# MJ818_original.net
KiCad netlist of a schematic drawn in EAGLE
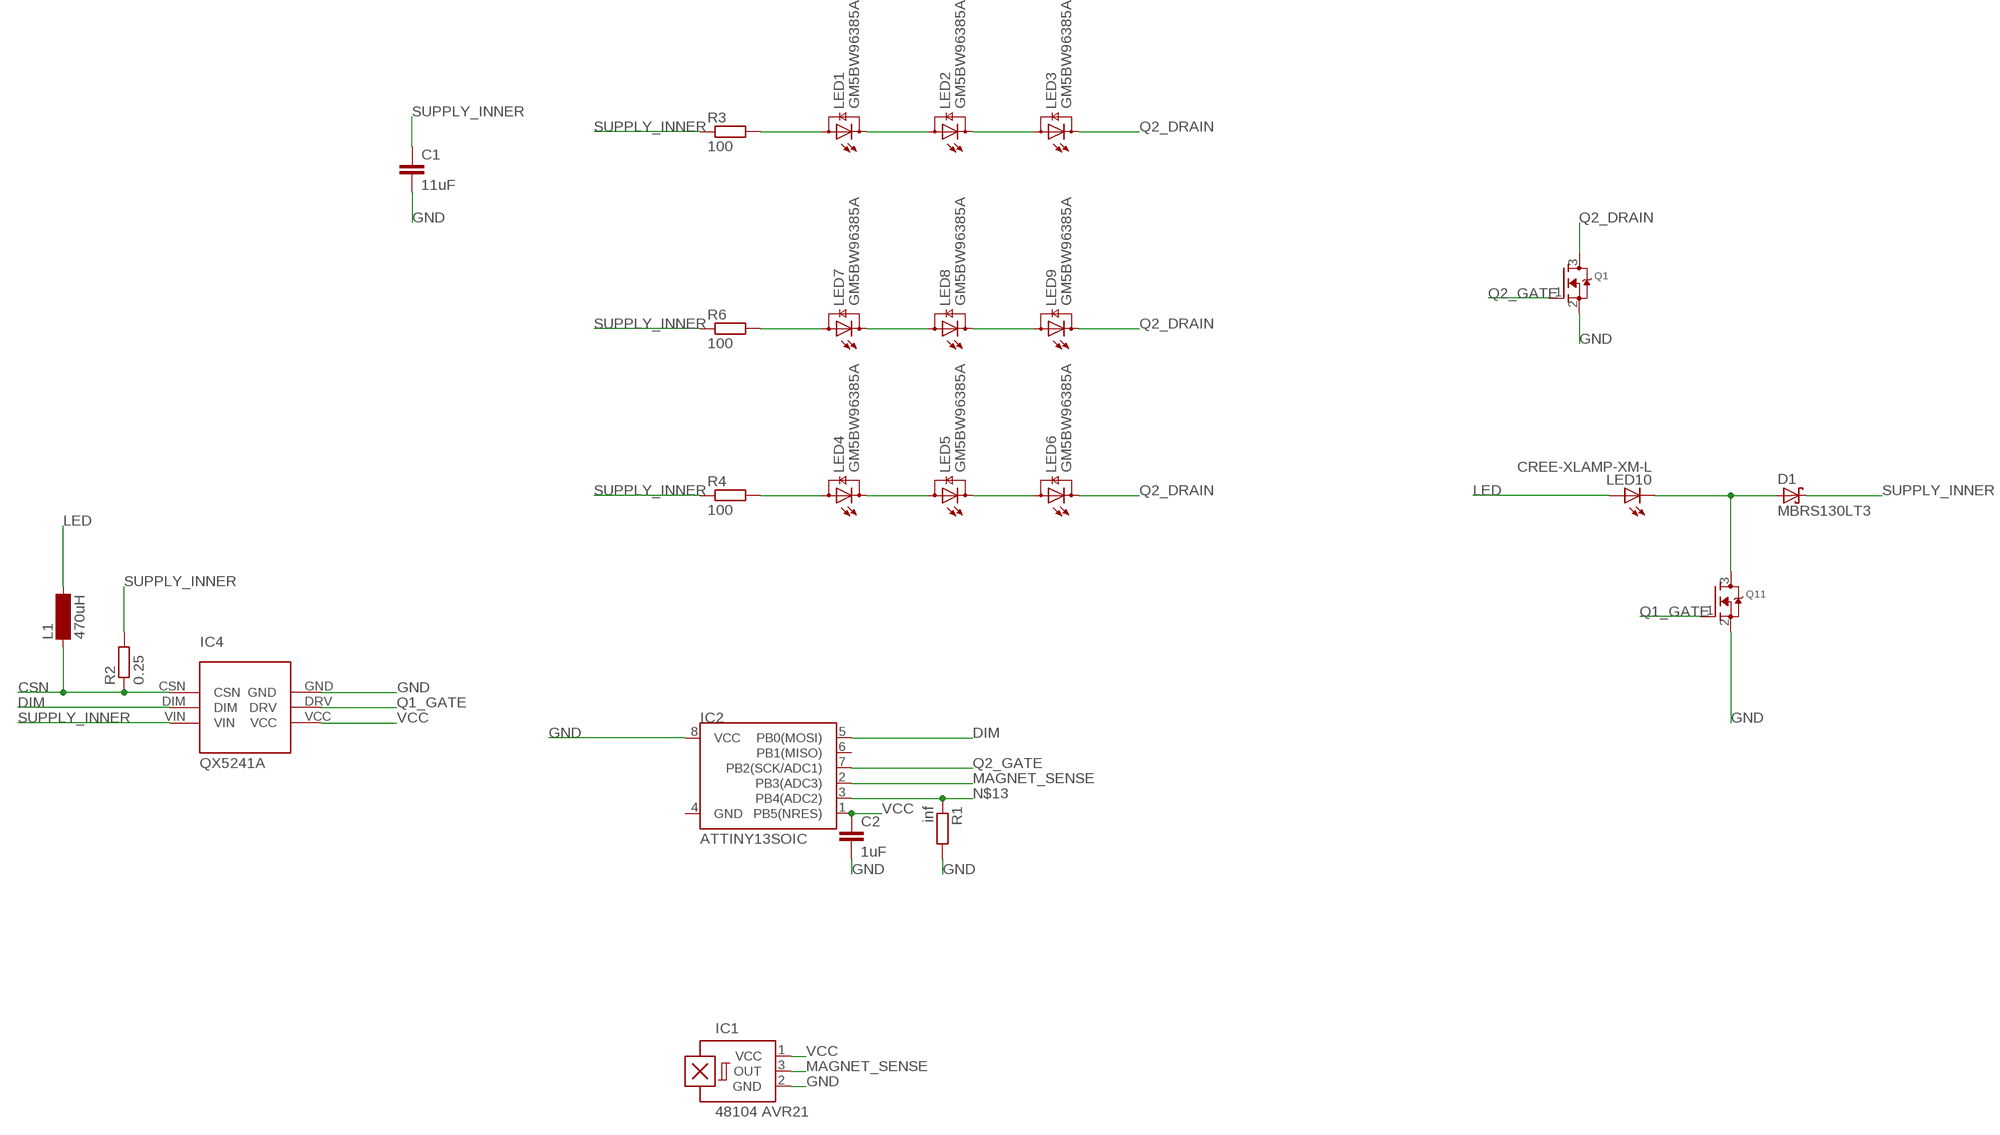
[diagram p0: schematic, sheet 1]

(export (version "E")
  (design (tool "Eeschema 10.0.6"))
  (components
    (comp (ref "C1")
      (value "11uF")
      (footprint "eagle-import:C3225")
      (libsource (lib "eagle-import") (part "C-EUC3225"))
    )
    (comp (ref "C2")
      (value "1uF")
      (footprint "eagle-import:C2012")
      (libsource (lib "eagle-import") (part "C-EUC2012"))
    )
    (comp (ref "D1")
      (value "MBRS130LT3")
      (footprint "eagle-import:SMB")
      (libsource (lib "eagle-import") (part "MBRS130LT3"))
    )
    (comp (ref "IC1")
      (value "48104 AVR21")
      (footprint "eagle-import:SIP3-UA")
      (libsource (lib "eagle-import") (part "A12?UA02"))
    )
    (comp (ref "IC2")
      (value "ATTINY13SOIC")
      (footprint "eagle-import:SO08_MCU")
      (libsource (lib "eagle-import") (part "ATTINY13SOIC"))
    )
    (comp (ref "IC4")
      (value "QX5241A")
      (footprint "eagle-import:SOT-23-6")
      (libsource (lib "eagle-import") (part "QX5241A"))
    )
    (comp (ref "L1")
      (value "470uH")
      (footprint "eagle-import:MS50")
      (libsource (lib "eagle-import") (part "MS50"))
    )
    (comp (ref "LED1")
      (value "GM5BW96385A")
      (footprint "eagle-import:GM5BW96385A")
      (libsource (lib "eagle-import") (part "GM5BW96385A"))
    )
    (comp (ref "LED2")
      (value "GM5BW96385A")
      (footprint "eagle-import:GM5BW96385A")
      (libsource (lib "eagle-import") (part "GM5BW96385A"))
    )
    (comp (ref "LED3")
      (value "GM5BW96385A")
      (footprint "eagle-import:GM5BW96385A")
      (libsource (lib "eagle-import") (part "GM5BW96385A"))
    )
    (comp (ref "LED4")
      (value "GM5BW96385A")
      (footprint "eagle-import:GM5BW96385A")
      (libsource (lib "eagle-import") (part "GM5BW96385A"))
    )
    (comp (ref "LED5")
      (value "GM5BW96385A")
      (footprint "eagle-import:GM5BW96385A")
      (libsource (lib "eagle-import") (part "GM5BW96385A"))
    )
    (comp (ref "LED6")
      (value "GM5BW96385A")
      (footprint "eagle-import:GM5BW96385A")
      (libsource (lib "eagle-import") (part "GM5BW96385A"))
    )
    (comp (ref "LED7")
      (value "GM5BW96385A")
      (footprint "eagle-import:GM5BW96385A")
      (libsource (lib "eagle-import") (part "GM5BW96385A"))
    )
    (comp (ref "LED8")
      (value "GM5BW96385A")
      (footprint "eagle-import:GM5BW96385A")
      (libsource (lib "eagle-import") (part "GM5BW96385A"))
    )
    (comp (ref "LED9")
      (value "GM5BW96385A")
      (footprint "eagle-import:GM5BW96385A")
      (libsource (lib "eagle-import") (part "GM5BW96385A"))
    )
    (comp (ref "LED10")
      (value "CREE-XLAMP-XM-L")
      (footprint "eagle-import:CREE-XLAMP-XM-L")
      (libsource (lib "eagle-import") (part "CREE-XLAMP-XM-L"))
    )
    (comp (ref "Q1")
      (value "MOSFET-NWAVE")
      (footprint "eagle-import:SOT23-W")
      (libsource (lib "eagle-import") (part "MOSFET-NWAVE"))
    )
    (comp (ref "Q11")
      (value "MOSFET-NWAVE")
      (footprint "eagle-import:SOT23-W")
      (libsource (lib "eagle-import") (part "MOSFET-NWAVE"))
    )
    (comp (ref "R1")
      (value "inf")
      (footprint "eagle-import:R3216")
      (libsource (lib "eagle-import") (part "R-EU_R3216"))
    )
    (comp (ref "R2")
      (value "0.25")
      (footprint "eagle-import:R3216")
      (libsource (lib "eagle-import") (part "R-EU_R3216"))
    )
    (comp (ref "R3")
      (value "100")
      (footprint "eagle-import:R3216")
      (libsource (lib "eagle-import") (part "R-EU_R3216"))
    )
    (comp (ref "R4")
      (value "100")
      (footprint "eagle-import:R3216")
      (libsource (lib "eagle-import") (part "R-EU_R3216"))
    )
    (comp (ref "R6")
      (value "100")
      (footprint "eagle-import:R3216")
      (libsource (lib "eagle-import") (part "R-EU_R3216"))
    )
  )
  (nets
    (net (code "1") (name "/CSN") (class "Default")
      (node (ref "IC4") (pin "CSN") (pinfunction "CSN_CSN") (pintype "bidirectional"))
      (node (ref "L1") (pin "1") (pinfunction "1_1") (pintype "passive"))
      (node (ref "R2") (pin "1") (pinfunction "1_1") (pintype "passive"))
    )
    (net (code "2") (name "/DIM") (class "Default")
      (node (ref "IC2") (pin "5") (pinfunction "PB0(MOSI)_5") (pintype "bidirectional"))
      (node (ref "IC4") (pin "DIM") (pinfunction "DIM_DIM") (pintype "bidirectional"))
    )
    (net (code "3") (name "/GND") (class "Default")
      (node (ref "C1") (pin "2") (pinfunction "2_2") (pintype "passive"))
      (node (ref "C2") (pin "2") (pinfunction "2_2") (pintype "passive"))
      (node (ref "IC1") (pin "2") (pinfunction "GND_2") (pintype "power_in"))
      (node (ref "IC2") (pin "8") (pinfunction "VCC_8") (pintype "bidirectional"))
      (node (ref "IC4") (pin "GND") (pinfunction "GND_GND") (pintype "bidirectional"))
      (node (ref "Q1") (pin "2") (pinfunction "S_2") (pintype "bidirectional"))
      (node (ref "Q11") (pin "2") (pinfunction "S_2") (pintype "bidirectional"))
      (node (ref "R1") (pin "2") (pinfunction "2_2") (pintype "passive"))
    )
    (net (code "4") (name "/LED") (class "Default")
      (node (ref "L1") (pin "2") (pinfunction "2_2") (pintype "passive"))
      (node (ref "LED10") (pin "A") (pinfunction "A_A") (pintype "passive"))
      (node (ref "LED10") (pin "A@1") (pinfunction "A_A@1") (pintype "passive"))
    )
    (net (code "5") (name "/MAGNET_SENSE") (class "Default")
      (node (ref "IC1") (pin "3") (pinfunction "OUT_3") (pintype "output"))
      (node (ref "IC2") (pin "2") (pinfunction "PB3(ADC3)_2") (pintype "bidirectional"))
    )
    (net (code "6") (name "/N$13") (class "Default")
      (node (ref "IC2") (pin "3") (pinfunction "PB4(ADC2)_3") (pintype "bidirectional"))
      (node (ref "R1") (pin "1") (pinfunction "1_1") (pintype "passive"))
    )
    (net (code "7") (name "/Q1_GATE") (class "Default")
      (node (ref "IC4") (pin "DRV") (pinfunction "DRV_DRV") (pintype "bidirectional"))
      (node (ref "Q11") (pin "1") (pinfunction "G_1") (pintype "bidirectional"))
    )
    (net (code "8") (name "/Q2_DRAIN") (class "Default")
      (node (ref "D1") (pin "A") (pinfunction "A_A") (pintype "passive"))
      (node (ref "LED10") (pin "C") (pinfunction "C_C") (pintype "passive"))
      (node (ref "LED10") (pin "C@1") (pinfunction "C_C@1") (pintype "passive"))
      (node (ref "LED3") (pin "C") (pinfunction "C_C") (pintype "passive"))
      (node (ref "LED6") (pin "C") (pinfunction "C_C") (pintype "passive"))
      (node (ref "LED9") (pin "C") (pinfunction "C_C") (pintype "passive"))
      (node (ref "Q1") (pin "3") (pinfunction "D_3") (pintype "bidirectional"))
      (node (ref "Q11") (pin "3") (pinfunction "D_3") (pintype "bidirectional"))
    )
    (net (code "9") (name "/Q2_GATE") (class "Default")
      (node (ref "IC2") (pin "7") (pinfunction "PB2(SCK/ADC1)_7") (pintype "bidirectional"))
      (node (ref "Q1") (pin "1") (pinfunction "G_1") (pintype "bidirectional"))
    )
    (net (code "10") (name "/SUPPLY_INNER") (class "Default")
      (node (ref "C1") (pin "1") (pinfunction "1_1") (pintype "passive"))
      (node (ref "D1") (pin "C") (pinfunction "C_C") (pintype "passive"))
      (node (ref "IC4") (pin "VIN") (pinfunction "VIN_VIN") (pintype "bidirectional"))
      (node (ref "R2") (pin "2") (pinfunction "2_2") (pintype "passive"))
      (node (ref "R3") (pin "1") (pinfunction "1_1") (pintype "passive"))
      (node (ref "R4") (pin "1") (pinfunction "1_1") (pintype "passive"))
      (node (ref "R6") (pin "1") (pinfunction "1_1") (pintype "passive"))
    )
    (net (code "11") (name "/VCC") (class "Default")
      (node (ref "C2") (pin "1") (pinfunction "1_1") (pintype "passive"))
      (node (ref "IC1") (pin "1") (pinfunction "VCC_1") (pintype "power_in"))
      (node (ref "IC2") (pin "1") (pinfunction "PB5(NRES)_1") (pintype "bidirectional"))
      (node (ref "IC4") (pin "VCC") (pinfunction "VCC_VCC") (pintype "bidirectional"))
    )
    (net (code "12") (name "Net-(LED1-PadA)") (class "Default")
      (node (ref "LED1") (pin "A") (pinfunction "A_A") (pintype "passive"))
      (node (ref "R3") (pin "2") (pinfunction "2_2") (pintype "passive"))
    )
    (net (code "13") (name "Net-(LED1-PadC)") (class "Default")
      (node (ref "LED1") (pin "C") (pinfunction "C_C") (pintype "passive"))
      (node (ref "LED2") (pin "A") (pinfunction "A_A") (pintype "passive"))
    )
    (net (code "14") (name "Net-(LED2-PadC)") (class "Default")
      (node (ref "LED2") (pin "C") (pinfunction "C_C") (pintype "passive"))
      (node (ref "LED3") (pin "A") (pinfunction "A_A") (pintype "passive"))
    )
    (net (code "15") (name "Net-(LED4-PadA)") (class "Default")
      (node (ref "LED4") (pin "A") (pinfunction "A_A") (pintype "passive"))
      (node (ref "R4") (pin "2") (pinfunction "2_2") (pintype "passive"))
    )
    (net (code "16") (name "Net-(LED4-PadC)") (class "Default")
      (node (ref "LED4") (pin "C") (pinfunction "C_C") (pintype "passive"))
      (node (ref "LED5") (pin "A") (pinfunction "A_A") (pintype "passive"))
    )
    (net (code "17") (name "Net-(LED5-PadC)") (class "Default")
      (node (ref "LED5") (pin "C") (pinfunction "C_C") (pintype "passive"))
      (node (ref "LED6") (pin "A") (pinfunction "A_A") (pintype "passive"))
    )
    (net (code "18") (name "Net-(LED7-PadA)") (class "Default")
      (node (ref "LED7") (pin "A") (pinfunction "A_A") (pintype "passive"))
      (node (ref "R6") (pin "2") (pinfunction "2_2") (pintype "passive"))
    )
    (net (code "19") (name "Net-(LED7-PadC)") (class "Default")
      (node (ref "LED7") (pin "C") (pinfunction "C_C") (pintype "passive"))
      (node (ref "LED8") (pin "A") (pinfunction "A_A") (pintype "passive"))
    )
    (net (code "20") (name "Net-(LED8-PadC)") (class "Default")
      (node (ref "LED8") (pin "C") (pinfunction "C_C") (pintype "passive"))
      (node (ref "LED9") (pin "A") (pinfunction "A_A") (pintype "passive"))
    )
    (net (code "21") (name "unconnected-(IC2-GND-Pad4)") (class "Default")
      (node (ref "IC2") (pin "4") (pinfunction "GND_4") (pintype "bidirectional"))
    )
    (net (code "22") (name "unconnected-(IC2-PB1(MISO)-Pad6)") (class "Default")
      (node (ref "IC2") (pin "6") (pinfunction "PB1(MISO)_6") (pintype "bidirectional"))
    )
  )
)
